# TIDA-010954-Top.net
KiCad netlist of a schematic drawn in Altium Designer
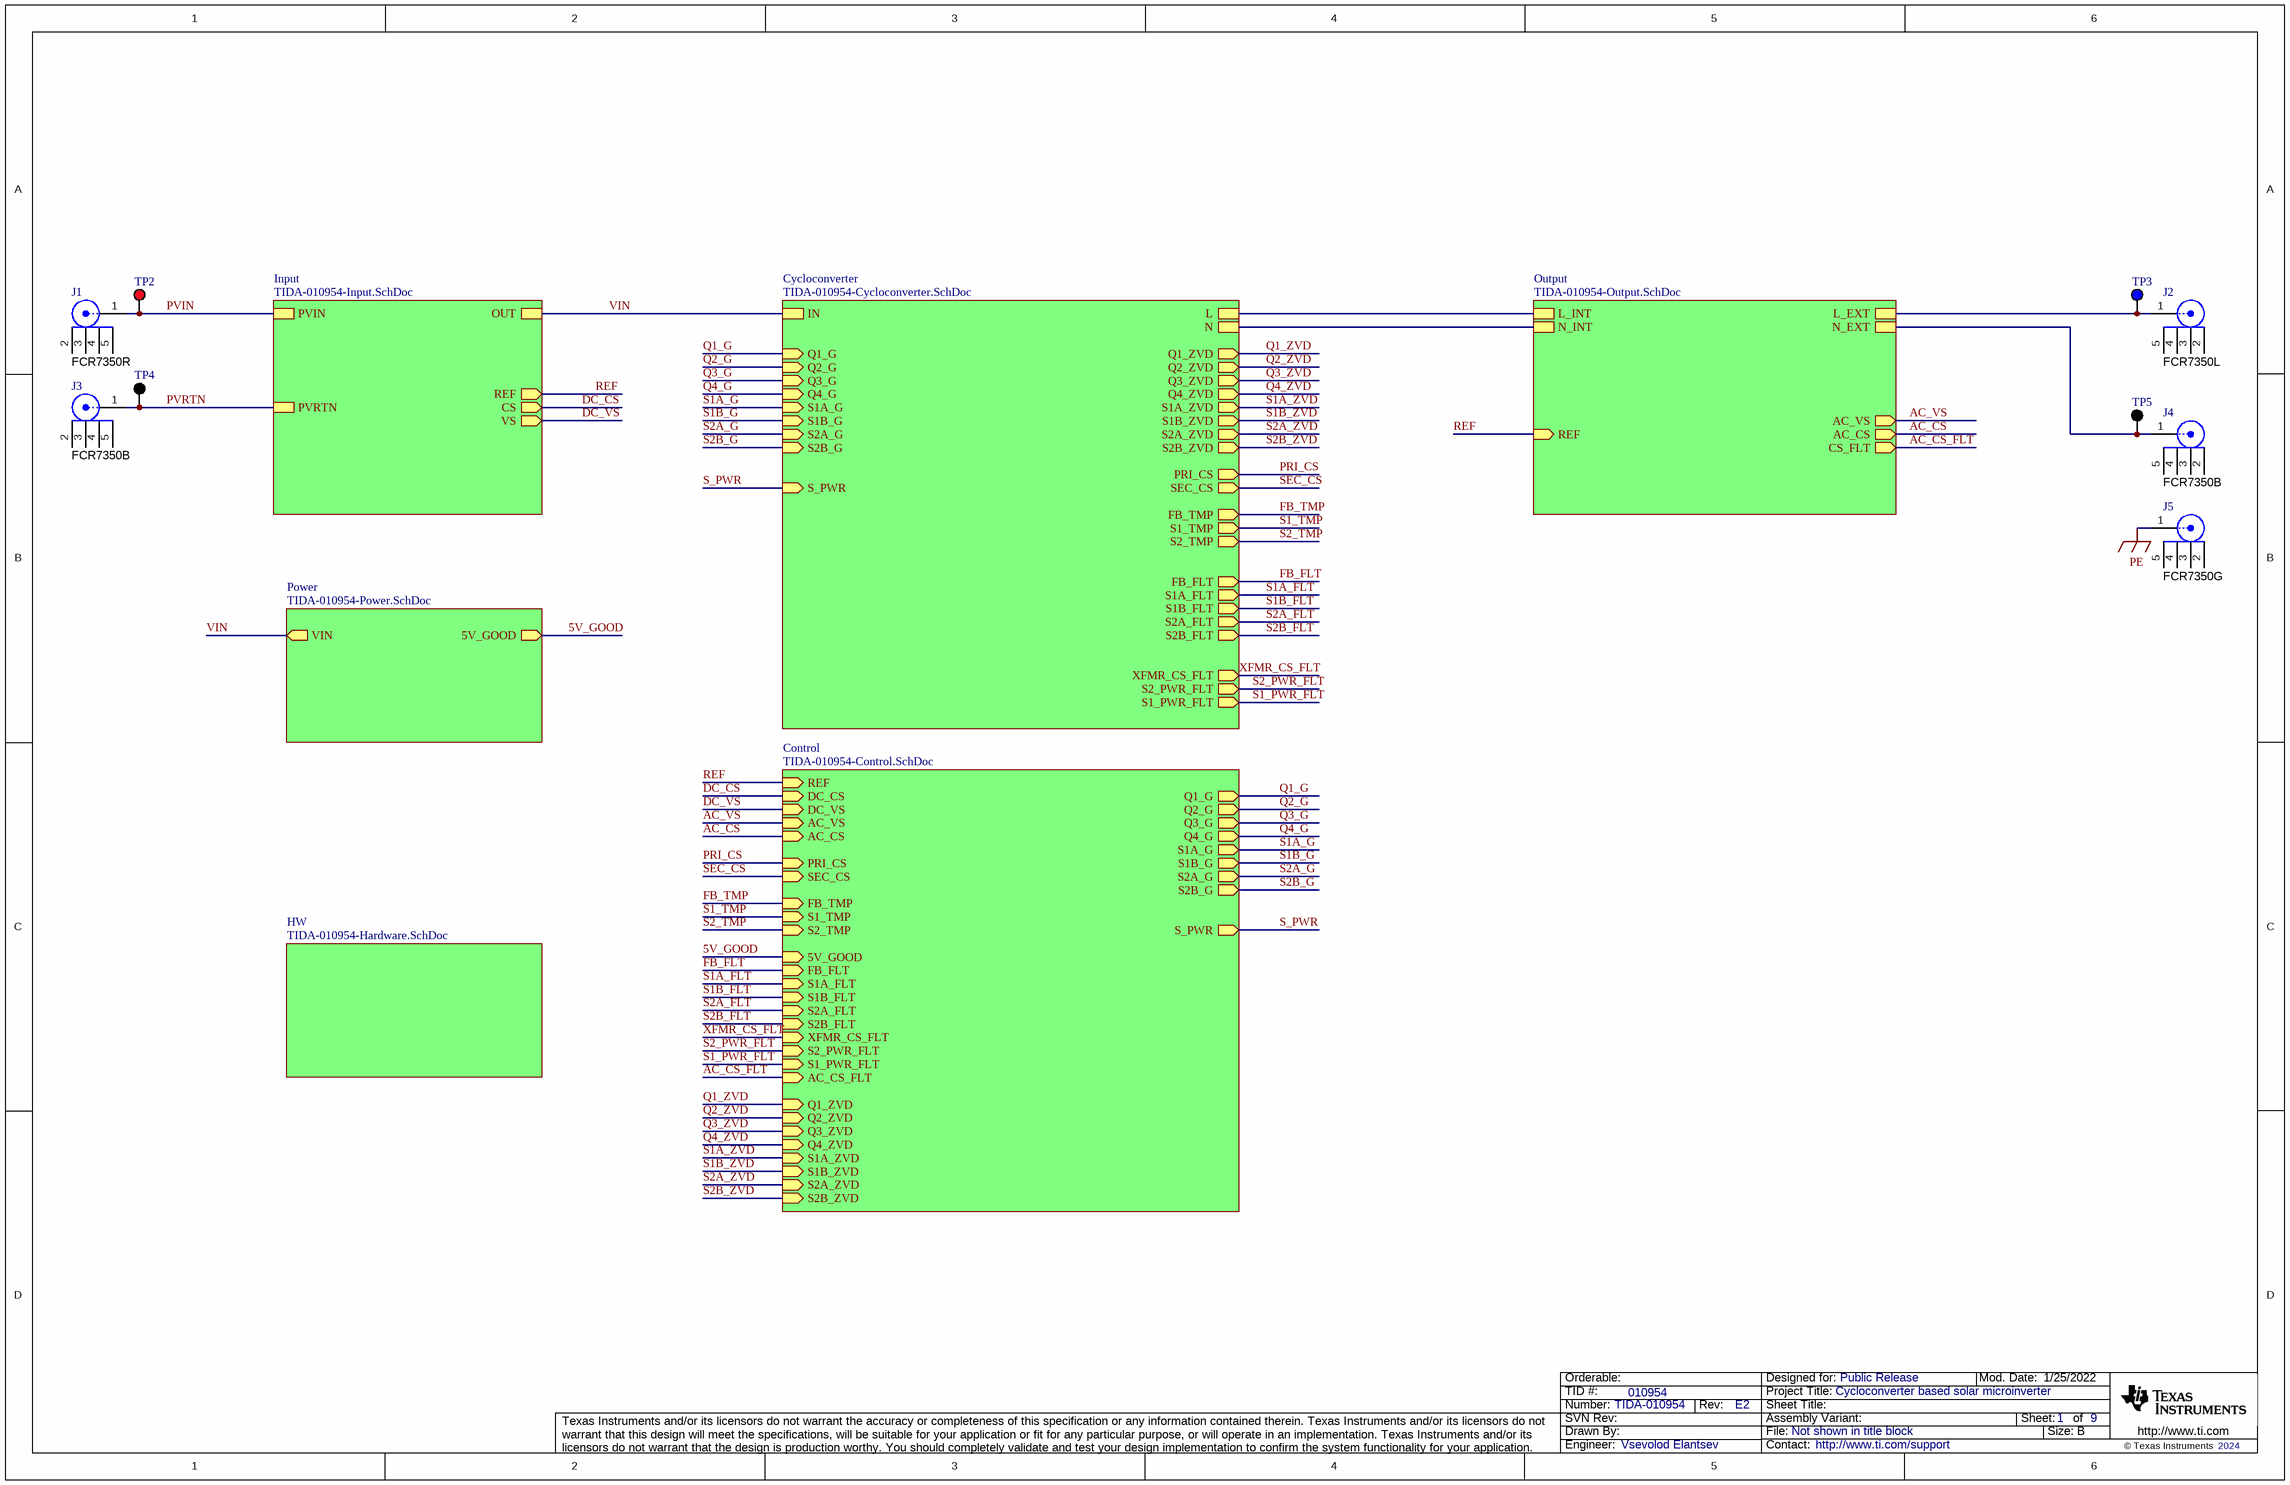
[diagram p0: TIDA-010954-Top.SchDoc]

(export (version "E")
  (design (tool "Eeschema 10.0.6"))
  (components
    (comp (ref "J1")
      (value "FCR7350R")
      (footprint "Cliff_FCR7350R")
      (description "Panel Socket, 24A, R/A, Gold, TH")
      (fields
        (field (name "MANUFACTURER") "Cliff Electronic Components")
        (field (name "PUBLISHER") "Texas Instruments")
      )
      (libsource (lib "Altium Vault - TI") (part "SMA_Contact1_GND2345"))
    )
    (comp (ref "J2")
      (value "FCR7350L")
      (footprint "FP-FCR7350L_CONN_BANANA_JACK-MFG")
      (description "Banana Test Connector, 4mm, Socket, PCB Mount, 24 A, 1 kV, Gold Plated Contacts, Blue")
      (fields (field (name "MANUFACTURER") "CLIFF Electronic Components"))
      (libsource (lib "Altium Vault - TI") (part "SMA_Contact1_GND2345"))
    )
    (comp (ref "J3")
      (value "FCR7350B")
      (footprint "Cliff_FCR7350B")
      (description "Panel Socket, 24A, R/A, Gold, TH")
      (fields
        (field (name "MANUFACTURER") "Cliff Electronic Components")
        (field (name "PUBLISHER") "Texas Instruments")
      )
      (libsource (lib "Altium Vault - TI") (part "SMA_Contact1_GND2345"))
    )
    (comp (ref "J4")
      (value "FCR7350B")
      (footprint "Cliff_FCR7350B")
      (description "Panel Socket, 24A, R/A, Gold, TH")
      (fields
        (field (name "MANUFACTURER") "Cliff Electronic Components")
        (field (name "PUBLISHER") "Texas Instruments")
      )
      (libsource (lib "Altium Vault - TI") (part "SMA_Contact1_GND2345"))
    )
    (comp (ref "J5")
      (value "FCR7350G")
      (footprint "FP-FCR7350G_CONN_BANANA_JACK-MFG")
      (description "Banana Test Connector, Socket, PCB Mount, 24 A, 1 kV, Gold Plated Contacts, Green")
      (fields
        (field (name "MANUFACTURER") "CLIFF Electronic Components")
        (field (name "DIGIKEY PART NUMBER") "4654-FCR7350G-ND")
      )
      (libsource (lib "Altium Vault - TI") (part "SMA_Contact1_GND2345"))
    )
    (comp (ref "TP2")
      (value "5010")
      (footprint "Keystone5010")
      (description "Test Point, Multipurpose, Red, TH")
      (fields
        (field (name "MANUFACTURER") "Keystone Electronics")
        (field (name "PUBLISHER") "Texas Instruments")
      )
      (libsource (lib "Altium Vault - TI") (part "5010"))
    )
    (comp (ref "TP3")
      (value "5127")
      (footprint "Keystone5127")
      (description "Test Point, Multipurpose, Blue, TH")
      (fields
        (field (name "MANUFACTURER") "Keystone Electronics")
        (field (name "PUBLISHER") "Texas Instruments")
      )
      (libsource (lib "Altium Vault - TI") (part "5127"))
    )
    (comp (ref "TP4")
      (value "5011")
      (footprint "Keystone5011")
      (description "Test Point, Multipurpose, Black, TH")
      (fields
        (field (name "MANUFACTURER") "Keystone Electronics")
        (field (name "PUBLISHER") "Texas Instruments")
      )
      (libsource (lib "Altium Vault - TI") (part "5011"))
    )
    (comp (ref "TP5")
      (value "5011")
      (footprint "Keystone5011")
      (description "Test Point, Multipurpose, Black, TH")
      (fields
        (field (name "MANUFACTURER") "Keystone Electronics")
        (field (name "PUBLISHER") "Texas Instruments")
      )
      (libsource (lib "Altium Vault - TI") (part "5011"))
    )
  )
  (nets
    (net (code "10") (name "/L_EXT") (class "Default")
      (node (ref "J2") (pin "1") (pinfunction "1_1") (pintype "passive"))
      (node (ref "TP3") (pin "1") (pintype "passive"))
    )
    (net (code "12") (name "/N_EXT") (class "Default")
      (node (ref "J4") (pin "1") (pinfunction "1_1") (pintype "passive"))
      (node (ref "TP5") (pin "1") (pintype "passive"))
    )
    (net (code "14") (name "/PVIN") (class "Default")
      (node (ref "J1") (pin "1") (pinfunction "1_1") (pintype "passive"))
      (node (ref "TP2") (pin "1") (pintype "passive"))
    )
    (net (code "15") (name "/PVRTN") (class "Default")
      (node (ref "J3") (pin "1") (pinfunction "1_1") (pintype "passive"))
      (node (ref "TP4") (pin "1") (pintype "passive"))
    )
    (net (code "45") (name "PE") (class "Default")
      (node (ref "J5") (pin "1") (pinfunction "1_1") (pintype "passive"))
    )
    (net (code "46") (name "unconnected-(J1-Pad2)") (class "Default")
      (node (ref "J1") (pin "2") (pinfunction "2_2") (pintype "passive"))
    )
    (net (code "47") (name "unconnected-(J1-Pad3)") (class "Default")
      (node (ref "J1") (pin "3") (pinfunction "3_3") (pintype "passive"))
    )
    (net (code "48") (name "unconnected-(J1-Pad4)") (class "Default")
      (node (ref "J1") (pin "4") (pinfunction "4_4") (pintype "passive"))
    )
    (net (code "49") (name "unconnected-(J1-Pad5)") (class "Default")
      (node (ref "J1") (pin "5") (pinfunction "5_5") (pintype "passive"))
    )
    (net (code "50") (name "unconnected-(J2-Pad2)") (class "Default")
      (node (ref "J2") (pin "2") (pinfunction "2_2") (pintype "passive"))
    )
    (net (code "51") (name "unconnected-(J2-Pad3)") (class "Default")
      (node (ref "J2") (pin "3") (pinfunction "3_3") (pintype "passive"))
    )
    (net (code "52") (name "unconnected-(J2-Pad4)") (class "Default")
      (node (ref "J2") (pin "4") (pinfunction "4_4") (pintype "passive"))
    )
    (net (code "53") (name "unconnected-(J2-Pad5)") (class "Default")
      (node (ref "J2") (pin "5") (pinfunction "5_5") (pintype "passive"))
    )
    (net (code "54") (name "unconnected-(J3-Pad2)") (class "Default")
      (node (ref "J3") (pin "2") (pinfunction "2_2") (pintype "passive"))
    )
    (net (code "55") (name "unconnected-(J3-Pad3)") (class "Default")
      (node (ref "J3") (pin "3") (pinfunction "3_3") (pintype "passive"))
    )
    (net (code "56") (name "unconnected-(J3-Pad4)") (class "Default")
      (node (ref "J3") (pin "4") (pinfunction "4_4") (pintype "passive"))
    )
    (net (code "57") (name "unconnected-(J3-Pad5)") (class "Default")
      (node (ref "J3") (pin "5") (pinfunction "5_5") (pintype "passive"))
    )
    (net (code "58") (name "unconnected-(J4-Pad2)") (class "Default")
      (node (ref "J4") (pin "2") (pinfunction "2_2") (pintype "passive"))
    )
    (net (code "59") (name "unconnected-(J4-Pad3)") (class "Default")
      (node (ref "J4") (pin "3") (pinfunction "3_3") (pintype "passive"))
    )
    (net (code "60") (name "unconnected-(J4-Pad4)") (class "Default")
      (node (ref "J4") (pin "4") (pinfunction "4_4") (pintype "passive"))
    )
    (net (code "61") (name "unconnected-(J4-Pad5)") (class "Default")
      (node (ref "J4") (pin "5") (pinfunction "5_5") (pintype "passive"))
    )
    (net (code "62") (name "unconnected-(J5-Pad2)") (class "Default")
      (node (ref "J5") (pin "2") (pinfunction "2_2") (pintype "passive"))
    )
    (net (code "63") (name "unconnected-(J5-Pad3)") (class "Default")
      (node (ref "J5") (pin "3") (pinfunction "3_3") (pintype "passive"))
    )
    (net (code "64") (name "unconnected-(J5-Pad4)") (class "Default")
      (node (ref "J5") (pin "4") (pinfunction "4_4") (pintype "passive"))
    )
    (net (code "65") (name "unconnected-(J5-Pad5)") (class "Default")
      (node (ref "J5") (pin "5") (pinfunction "5_5") (pintype "passive"))
    )
  )
)
